# Module_20200402_1_FlexSensorAdapter.net
KiCad netlist of a schematic drawn in EAGLE
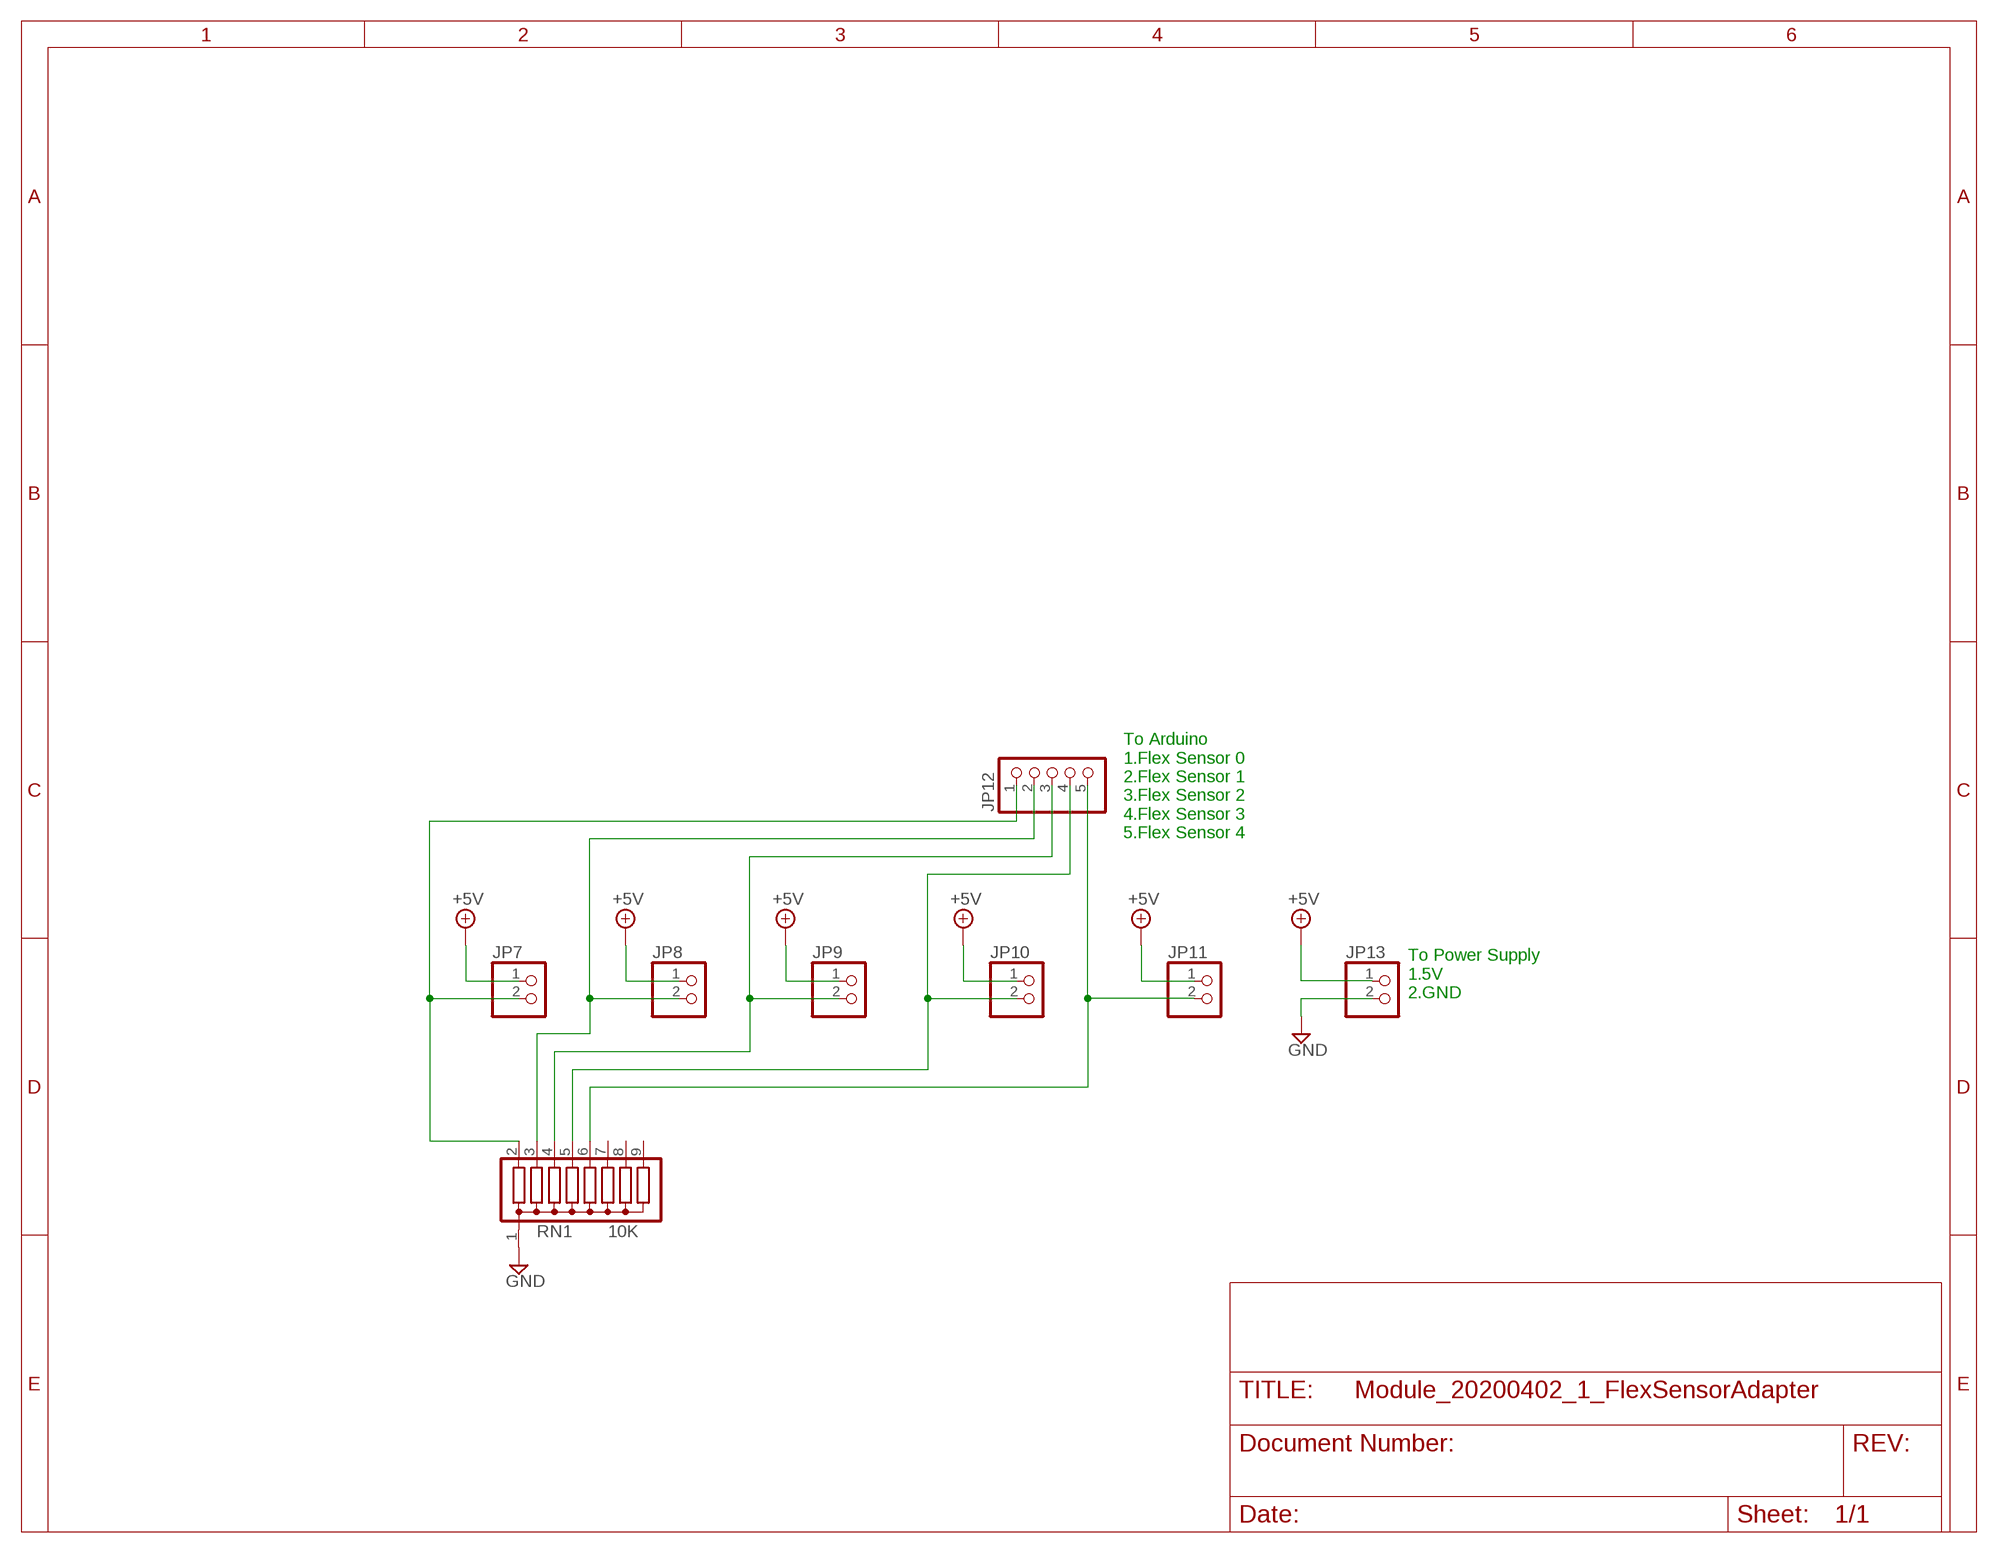
[diagram p0: schematic, sheet 1]

(export (version "E")
  (design (tool "Eeschema 10.0.6"))
  (components
    (comp (ref "JP7")
      (value "PINHD-1X2")
      (footprint "eagle-import:1X02")
      (libsource (lib "eagle-import") (part "PINHD-1X2"))
    )
    (comp (ref "JP8")
      (value "PINHD-1X2")
      (footprint "eagle-import:1X02")
      (libsource (lib "eagle-import") (part "PINHD-1X2"))
    )
    (comp (ref "JP9")
      (value "PINHD-1X2")
      (footprint "eagle-import:1X02")
      (libsource (lib "eagle-import") (part "PINHD-1X2"))
    )
    (comp (ref "JP10")
      (value "PINHD-1X2")
      (footprint "eagle-import:1X02")
      (libsource (lib "eagle-import") (part "PINHD-1X2"))
    )
    (comp (ref "JP11")
      (value "PINHD-1X2")
      (footprint "eagle-import:1X02")
      (libsource (lib "eagle-import") (part "PINHD-1X2"))
    )
    (comp (ref "JP12")
      (value "PINHD-1X5")
      (footprint "eagle-import:1X05")
      (libsource (lib "eagle-import") (part "PINHD-1X5"))
    )
    (comp (ref "JP13")
      (value "PINHD-1X2")
      (footprint "eagle-import:1X02")
      (libsource (lib "eagle-import") (part "PINHD-1X2"))
    )
    (comp (ref "RN1")
      (value "10K")
      (footprint "eagle-import:SIL9")
      (libsource (lib "eagle-import") (part "G08R"))
    )
  )
  (nets
    (net (code "1") (name "+5V") (class "Default")
      (node (ref "JP10") (pin "1") (pinfunction "1_1") (pintype "passive"))
      (node (ref "JP11") (pin "1") (pinfunction "1_1") (pintype "passive"))
      (node (ref "JP13") (pin "1") (pinfunction "1_1") (pintype "passive"))
      (node (ref "JP7") (pin "1") (pinfunction "1_1") (pintype "passive"))
      (node (ref "JP8") (pin "1") (pinfunction "1_1") (pintype "passive"))
      (node (ref "JP9") (pin "1") (pinfunction "1_1") (pintype "passive"))
    )
    (net (code "2") (name "GND") (class "Default")
      (node (ref "JP13") (pin "2") (pinfunction "2_2") (pintype "passive"))
      (node (ref "RN1") (pin "1") (pinfunction "1_1") (pintype "passive"))
    )
    (net (code "3") (name "Net-(JP10-Pad2)") (class "Default")
      (node (ref "JP10") (pin "2") (pinfunction "2_2") (pintype "passive"))
      (node (ref "JP12") (pin "4") (pinfunction "4_4") (pintype "passive"))
      (node (ref "RN1") (pin "5") (pinfunction "5_5") (pintype "passive"))
    )
    (net (code "4") (name "Net-(JP11-Pad2)") (class "Default")
      (node (ref "JP11") (pin "2") (pinfunction "2_2") (pintype "passive"))
      (node (ref "JP12") (pin "5") (pinfunction "5_5") (pintype "passive"))
      (node (ref "RN1") (pin "6") (pinfunction "6_6") (pintype "passive"))
    )
    (net (code "5") (name "Net-(JP12-Pad1)") (class "Default")
      (node (ref "JP12") (pin "1") (pinfunction "1_1") (pintype "passive"))
      (node (ref "JP7") (pin "2") (pinfunction "2_2") (pintype "passive"))
      (node (ref "RN1") (pin "2") (pinfunction "2_2") (pintype "passive"))
    )
    (net (code "6") (name "Net-(JP12-Pad2)") (class "Default")
      (node (ref "JP12") (pin "2") (pinfunction "2_2") (pintype "passive"))
      (node (ref "JP8") (pin "2") (pinfunction "2_2") (pintype "passive"))
      (node (ref "RN1") (pin "3") (pinfunction "3_3") (pintype "passive"))
    )
    (net (code "7") (name "Net-(JP12-Pad3)") (class "Default")
      (node (ref "JP12") (pin "3") (pinfunction "3_3") (pintype "passive"))
      (node (ref "JP9") (pin "2") (pinfunction "2_2") (pintype "passive"))
      (node (ref "RN1") (pin "4") (pinfunction "4_4") (pintype "passive"))
    )
    (net (code "8") (name "unconnected-(RN1-Pad7)") (class "Default")
      (node (ref "RN1") (pin "7") (pinfunction "7_7") (pintype "passive"))
    )
    (net (code "9") (name "unconnected-(RN1-Pad8)") (class "Default")
      (node (ref "RN1") (pin "8") (pinfunction "8_8") (pintype "passive"))
    )
    (net (code "10") (name "unconnected-(RN1-Pad9)") (class "Default")
      (node (ref "RN1") (pin "9") (pinfunction "9_9") (pintype "passive"))
    )
  )
)
